# PIC-adresseur.net
KiCad netlist of a schematic drawn in EAGLE
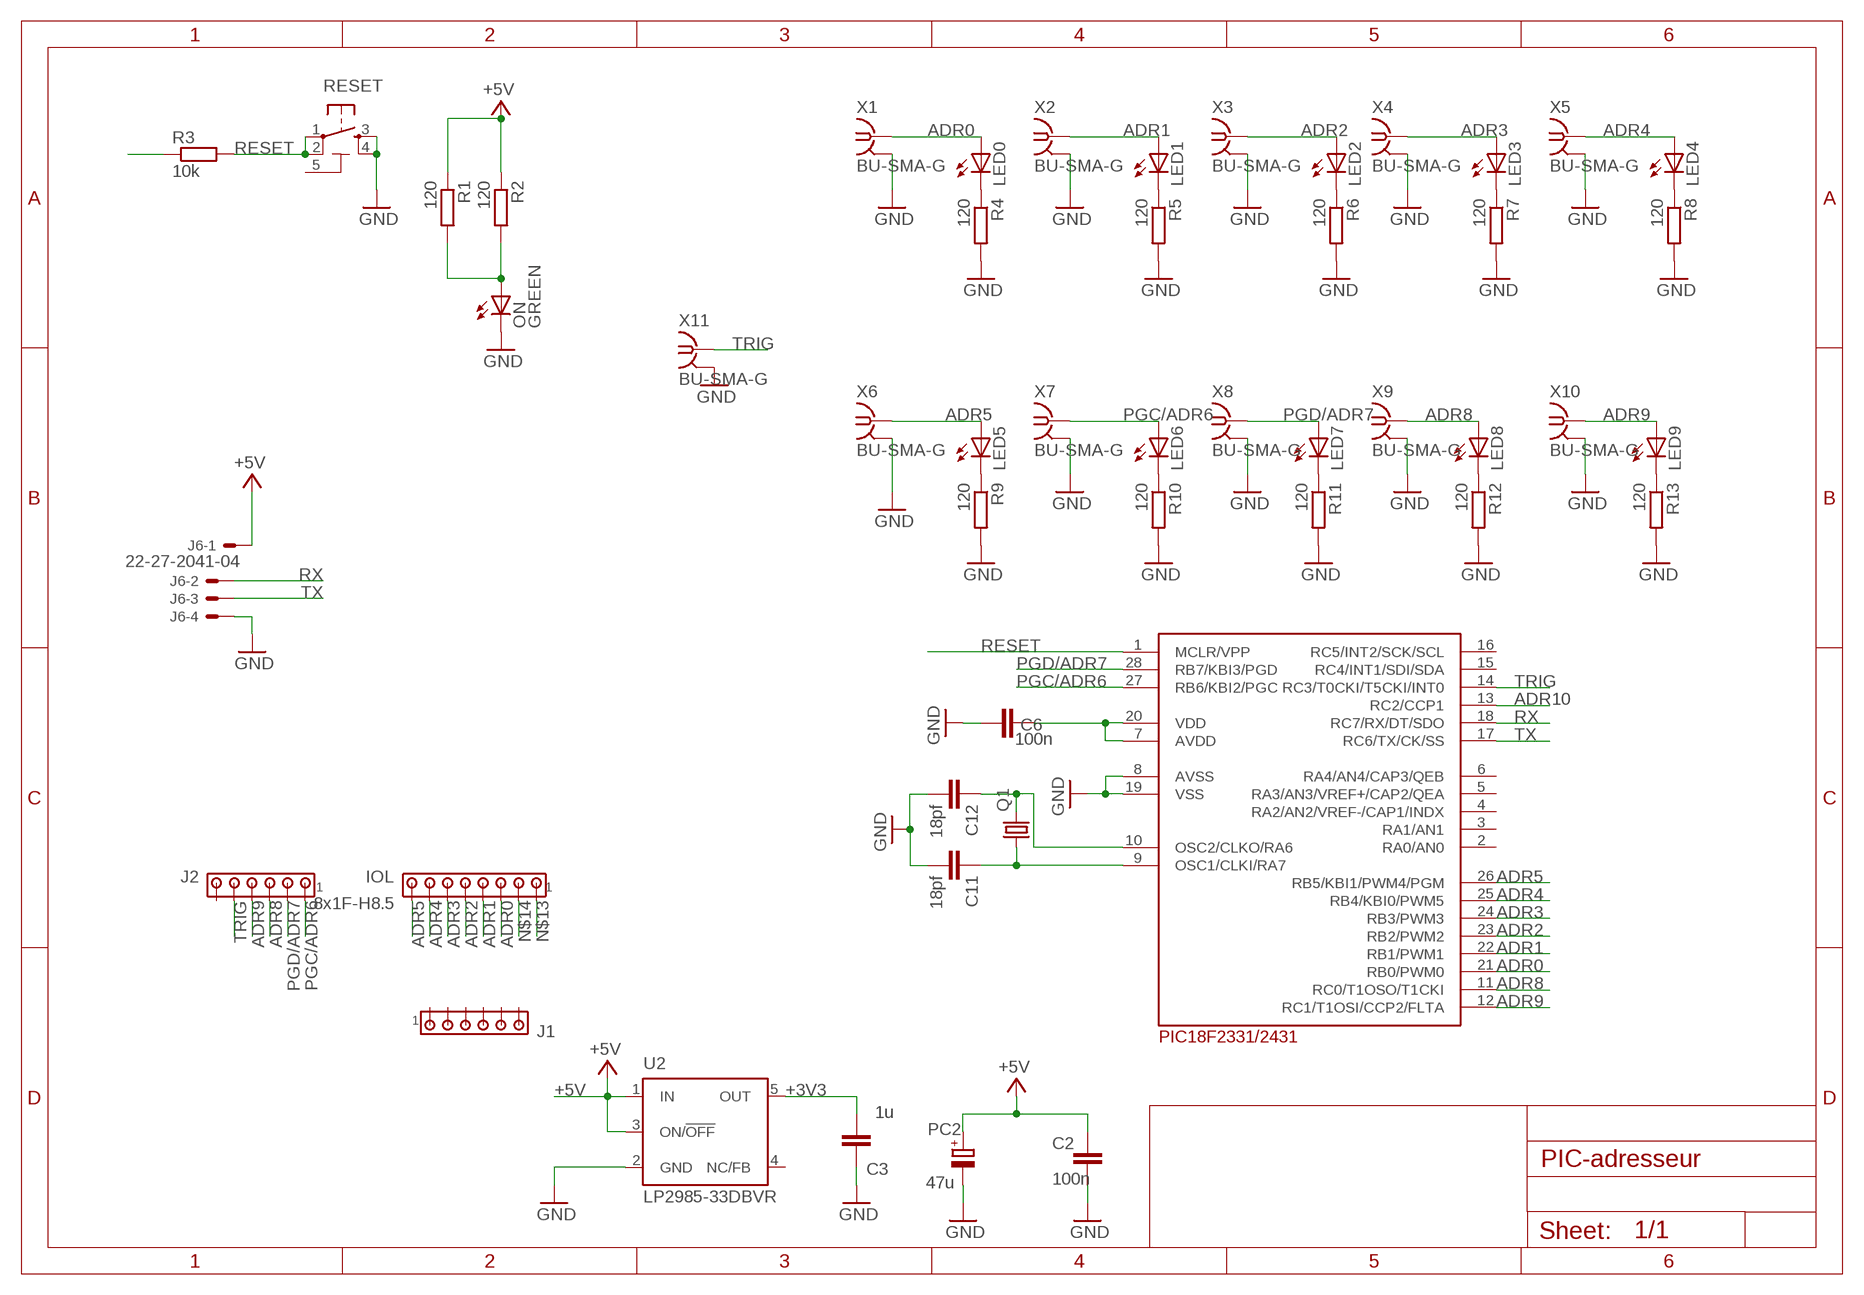
[diagram p0: schematic, sheet 1]

(export (version "E")
  (design (tool "Eeschema 10.0.6"))
  (components
    (comp (ref "C2")
      (value "100n")
      (footprint "eagle-import:C0603-ROUND")
      (libsource (lib "eagle-import") (part "C-EU0603-RND"))
    )
    (comp (ref "C3")
      (value "1u")
      (footprint "eagle-import:C0603-ROUND")
      (libsource (lib "eagle-import") (part "C-EU0603-RND"))
    )
    (comp (ref "C6")
      (value "100n")
      (footprint "eagle-import:C0603K")
      (libsource (lib "eagle-import") (part "SmartPrj_C-EUC0603K"))
    )
    (comp (ref "C11")
      (value "18pf")
      (footprint "eagle-import:C0603")
      (libsource (lib "eagle-import") (part "C-EUC0603"))
    )
    (comp (ref "C12")
      (value "18pf")
      (footprint "eagle-import:C0603")
      (libsource (lib "eagle-import") (part "C-EUC0603"))
    )
    (comp (ref "IOL")
      (value "8x1F-H8.5")
      (footprint "eagle-import:10X08MTA")
      (libsource (lib "eagle-import") (part "MTA08-100"))
    )
    (comp (ref "J1")
      (value "MTA06-100")
      (footprint "eagle-import:10X06MTA")
      (libsource (lib "eagle-import") (part "MTA06-100"))
    )
    (comp (ref "J2")
      (value "MTA06-100")
      (footprint "eagle-import:10X06MTA")
      (libsource (lib "eagle-import") (part "MTA06-100"))
    )
    (comp (ref "J6")
      (value "22-27-2041-04")
      (footprint "eagle-import:6410-04")
      (libsource (lib "eagle-import") (part "22-?-0427-2041"))
    )
    (comp (ref "LED0")
      (value "LEDCHIP-LED0805")
      (footprint "eagle-import:CHIP-LED0805")
      (libsource (lib "eagle-import") (part "LEDCHIP-LED0805"))
    )
    (comp (ref "LED1")
      (value "LEDCHIP-LED0805")
      (footprint "eagle-import:CHIP-LED0805")
      (libsource (lib "eagle-import") (part "LEDCHIP-LED0805"))
    )
    (comp (ref "LED2")
      (value "LEDCHIP-LED0805")
      (footprint "eagle-import:CHIP-LED0805")
      (libsource (lib "eagle-import") (part "LEDCHIP-LED0805"))
    )
    (comp (ref "LED3")
      (value "LEDCHIP-LED0805")
      (footprint "eagle-import:CHIP-LED0805")
      (libsource (lib "eagle-import") (part "LEDCHIP-LED0805"))
    )
    (comp (ref "LED4")
      (value "LEDCHIP-LED0805")
      (footprint "eagle-import:CHIP-LED0805")
      (libsource (lib "eagle-import") (part "LEDCHIP-LED0805"))
    )
    (comp (ref "LED5")
      (value "LEDCHIP-LED0805")
      (footprint "eagle-import:CHIP-LED0805")
      (libsource (lib "eagle-import") (part "LEDCHIP-LED0805"))
    )
    (comp (ref "LED6")
      (value "LEDCHIP-LED0805")
      (footprint "eagle-import:CHIP-LED0805")
      (libsource (lib "eagle-import") (part "LEDCHIP-LED0805"))
    )
    (comp (ref "LED7")
      (value "LEDCHIP-LED0805")
      (footprint "eagle-import:CHIP-LED0805")
      (libsource (lib "eagle-import") (part "LEDCHIP-LED0805"))
    )
    (comp (ref "LED8")
      (value "LEDCHIP-LED0805")
      (footprint "eagle-import:CHIP-LED0805")
      (libsource (lib "eagle-import") (part "LEDCHIP-LED0805"))
    )
    (comp (ref "LED9")
      (value "LEDCHIP-LED0805")
      (footprint "eagle-import:CHIP-LED0805")
      (libsource (lib "eagle-import") (part "LEDCHIP-LED0805"))
    )
    (comp (ref "ON")
      (value "GREEN")
      (footprint "eagle-import:CHIP-LED0805")
      (libsource (lib "eagle-import") (part "led_LEDCHIP-LED0805"))
    )
    (comp (ref "PC2")
      (value "47u")
      (footprint "eagle-import:PANASONIC_D")
      (libsource (lib "eagle-import") (part "CPOL-EUD"))
    )
    (comp (ref "Q1")
      (value "CRYSTALSM49")
      (footprint "eagle-import:SM49")
      (fields (field (name "OC_FARNELL") "1842332"))
      (libsource (lib "eagle-import") (part "CRYSTALSM49"))
    )
    (comp (ref "R1")
      (value "120")
      (footprint "eagle-import:R0805")
      (libsource (lib "eagle-import") (part "R-EU_R0805"))
    )
    (comp (ref "R2")
      (value "120")
      (footprint "eagle-import:R0805")
      (libsource (lib "eagle-import") (part "R-EU_R0805"))
    )
    (comp (ref "R3")
      (value "10k")
      (footprint "eagle-import:R0805")
      (libsource (lib "eagle-import") (part "R-EU_R0805"))
    )
    (comp (ref "R4")
      (value "120")
      (footprint "eagle-import:R0805")
      (libsource (lib "eagle-import") (part "R-EU_R0805"))
    )
    (comp (ref "R5")
      (value "120")
      (footprint "eagle-import:R0805")
      (libsource (lib "eagle-import") (part "R-EU_R0805"))
    )
    (comp (ref "R6")
      (value "120")
      (footprint "eagle-import:R0805")
      (libsource (lib "eagle-import") (part "R-EU_R0805"))
    )
    (comp (ref "R7")
      (value "120")
      (footprint "eagle-import:R0805")
      (libsource (lib "eagle-import") (part "R-EU_R0805"))
    )
    (comp (ref "R8")
      (value "120")
      (footprint "eagle-import:R0805")
      (libsource (lib "eagle-import") (part "R-EU_R0805"))
    )
    (comp (ref "R9")
      (value "120")
      (footprint "eagle-import:R0805")
      (libsource (lib "eagle-import") (part "R-EU_R0805"))
    )
    (comp (ref "R10")
      (value "120")
      (footprint "eagle-import:R0805")
      (libsource (lib "eagle-import") (part "R-EU_R0805"))
    )
    (comp (ref "R11")
      (value "120")
      (footprint "eagle-import:R0805")
      (libsource (lib "eagle-import") (part "R-EU_R0805"))
    )
    (comp (ref "R12")
      (value "120")
      (footprint "eagle-import:R0805")
      (libsource (lib "eagle-import") (part "R-EU_R0805"))
    )
    (comp (ref "R13")
      (value "120")
      (footprint "eagle-import:R0805")
      (libsource (lib "eagle-import") (part "R-EU_R0805"))
    )
    (comp (ref "RESET")
      (value "TS42031-160R-TR-7260")
      (footprint "eagle-import:TS42")
      (libsource (lib "eagle-import") (part "TS42"))
    )
    (comp (ref "U$2")
      (value "PIC18F2331/2431")
      (footprint "eagle-import:DIL28-3")
      (libsource (lib "eagle-import") (part "PIC18F2331/2431"))
    )
    (comp (ref "U2")
      (value "LP2985-33DBVR")
      (footprint "eagle-import:SOT23-DBV")
      (libsource (lib "eagle-import") (part "LP2985-XXDBVR33"))
    )
    (comp (ref "X1")
      (value "BU-SMA-G")
      (footprint "eagle-import:BU-SMA-G")
      (libsource (lib "eagle-import") (part "BU-SMA-G"))
    )
    (comp (ref "X2")
      (value "BU-SMA-G")
      (footprint "eagle-import:BU-SMA-G")
      (libsource (lib "eagle-import") (part "BU-SMA-G"))
    )
    (comp (ref "X3")
      (value "BU-SMA-G")
      (footprint "eagle-import:BU-SMA-G")
      (libsource (lib "eagle-import") (part "BU-SMA-G"))
    )
    (comp (ref "X4")
      (value "BU-SMA-G")
      (footprint "eagle-import:BU-SMA-G")
      (libsource (lib "eagle-import") (part "BU-SMA-G"))
    )
    (comp (ref "X5")
      (value "BU-SMA-G")
      (footprint "eagle-import:BU-SMA-G")
      (libsource (lib "eagle-import") (part "BU-SMA-G"))
    )
    (comp (ref "X6")
      (value "BU-SMA-G")
      (footprint "eagle-import:BU-SMA-G")
      (libsource (lib "eagle-import") (part "BU-SMA-G"))
    )
    (comp (ref "X7")
      (value "BU-SMA-G")
      (footprint "eagle-import:BU-SMA-G")
      (libsource (lib "eagle-import") (part "BU-SMA-G"))
    )
    (comp (ref "X8")
      (value "BU-SMA-G")
      (footprint "eagle-import:BU-SMA-G")
      (libsource (lib "eagle-import") (part "BU-SMA-G"))
    )
    (comp (ref "X9")
      (value "BU-SMA-G")
      (footprint "eagle-import:BU-SMA-G")
      (libsource (lib "eagle-import") (part "BU-SMA-G"))
    )
    (comp (ref "X10")
      (value "BU-SMA-G")
      (footprint "eagle-import:BU-SMA-G")
      (libsource (lib "eagle-import") (part "BU-SMA-G"))
    )
    (comp (ref "X11")
      (value "BU-SMA-G")
      (footprint "eagle-import:BU-SMA-G")
      (libsource (lib "eagle-import") (part "BU-SMA-G"))
    )
  )
  (nets
    (net (code "1") (name "+5V") (class "Default")
      (node (ref "C2") (pin "2") (pinfunction "2_2") (pintype "passive"))
      (node (ref "J6") (pin "1") (pinfunction "S_1") (pintype "passive"))
      (node (ref "PC2") (pin "+") (pinfunction "+_+") (pintype "passive"))
      (node (ref "R1") (pin "1") (pinfunction "1_1") (pintype "passive"))
      (node (ref "R2") (pin "1") (pinfunction "1_1") (pintype "passive"))
      (node (ref "U2") (pin "1") (pinfunction "IN_1") (pintype "input"))
      (node (ref "U2") (pin "3") (pinfunction "ON/~{OFF}_3") (pintype "input"))
    )
    (net (code "2") (name "/+3V3") (class "Default")
      (node (ref "C3") (pin "2") (pinfunction "2_2") (pintype "passive"))
      (node (ref "C6") (pin "2") (pinfunction "2_2") (pintype "passive"))
      (node (ref "R3") (pin "1") (pinfunction "1_1") (pintype "passive"))
      (node (ref "U$2") (pin "20") (pinfunction "VDD_20") (pintype "bidirectional"))
      (node (ref "U$2") (pin "7") (pinfunction "AVDD_7") (pintype "bidirectional"))
      (node (ref "U2") (pin "5") (pinfunction "OUT_5") (pintype "passive"))
    )
    (net (code "3") (name "/5-GND") (class "Default")
      (node (ref "RESET") (pin "5") (pinfunction "5-GND_5") (pintype "power_in"))
    )
    (net (code "4") (name "/ADR0") (class "Default")
      (node (ref "IOL") (pin "3") (pinfunction "3_3") (pintype "passive"))
      (node (ref "LED0") (pin "A") (pinfunction "A_A") (pintype "passive"))
      (node (ref "U$2") (pin "21") (pinfunction "RB0/PWM0_21") (pintype "bidirectional"))
      (node (ref "X1") (pin "1") (pinfunction "1_1") (pintype "passive"))
    )
    (net (code "5") (name "/ADR1") (class "Default")
      (node (ref "IOL") (pin "4") (pinfunction "4_4") (pintype "passive"))
      (node (ref "LED1") (pin "A") (pinfunction "A_A") (pintype "passive"))
      (node (ref "U$2") (pin "22") (pinfunction "RB1/PWM1_22") (pintype "bidirectional"))
      (node (ref "X2") (pin "1") (pinfunction "1_1") (pintype "passive"))
    )
    (net (code "6") (name "/ADR2") (class "Default")
      (node (ref "IOL") (pin "5") (pinfunction "5_5") (pintype "passive"))
      (node (ref "LED2") (pin "A") (pinfunction "A_A") (pintype "passive"))
      (node (ref "U$2") (pin "23") (pinfunction "RB2/PWM2_23") (pintype "bidirectional"))
      (node (ref "X3") (pin "1") (pinfunction "1_1") (pintype "passive"))
    )
    (net (code "7") (name "/ADR3") (class "Default")
      (node (ref "IOL") (pin "6") (pinfunction "6_6") (pintype "passive"))
      (node (ref "LED3") (pin "A") (pinfunction "A_A") (pintype "passive"))
      (node (ref "U$2") (pin "24") (pinfunction "RB3/PWM3_24") (pintype "bidirectional"))
      (node (ref "X4") (pin "1") (pinfunction "1_1") (pintype "passive"))
    )
    (net (code "8") (name "/ADR4") (class "Default")
      (node (ref "IOL") (pin "7") (pinfunction "7_7") (pintype "passive"))
      (node (ref "LED4") (pin "A") (pinfunction "A_A") (pintype "passive"))
      (node (ref "U$2") (pin "25") (pinfunction "RB4/KBI0/PWM5_25") (pintype "bidirectional"))
      (node (ref "X5") (pin "1") (pinfunction "1_1") (pintype "passive"))
    )
    (net (code "9") (name "/ADR5") (class "Default")
      (node (ref "IOL") (pin "8") (pinfunction "8_8") (pintype "passive"))
      (node (ref "LED5") (pin "A") (pinfunction "A_A") (pintype "passive"))
      (node (ref "U$2") (pin "26") (pinfunction "RB5/KBI1/PWM4/PGM_26") (pintype "bidirectional"))
      (node (ref "X6") (pin "1") (pinfunction "1_1") (pintype "passive"))
    )
    (net (code "10") (name "/ADR8") (class "Default")
      (node (ref "J2") (pin "4") (pinfunction "3_4") (pintype "passive"))
      (node (ref "LED8") (pin "A") (pinfunction "A_A") (pintype "passive"))
      (node (ref "U$2") (pin "11") (pinfunction "RC0/T1OSO/T1CKI_11") (pintype "bidirectional"))
      (node (ref "X9") (pin "1") (pinfunction "1_1") (pintype "passive"))
    )
    (net (code "11") (name "/ADR9") (class "Default")
      (node (ref "J2") (pin "3") (pinfunction "4_3") (pintype "passive"))
      (node (ref "LED9") (pin "A") (pinfunction "A_A") (pintype "passive"))
      (node (ref "U$2") (pin "12") (pinfunction "RC1/T1OSI/CCP2/FLTA_12") (pintype "bidirectional"))
      (node (ref "X10") (pin "1") (pinfunction "1_1") (pintype "passive"))
    )
    (net (code "12") (name "/ADR10") (class "Default")
      (node (ref "U$2") (pin "13") (pinfunction "RC2/CCP1_13") (pintype "bidirectional"))
    )
    (net (code "13") (name "/N$13") (class "Default")
      (node (ref "IOL") (pin "1") (pinfunction "1_1") (pintype "passive"))
    )
    (net (code "14") (name "/N$14") (class "Default")
      (node (ref "IOL") (pin "2") (pinfunction "2_2") (pintype "passive"))
    )
    (net (code "15") (name "/PGC{slash}ADR6") (class "Default")
      (node (ref "J2") (pin "6") (pinfunction "1_6") (pintype "passive"))
      (node (ref "LED6") (pin "A") (pinfunction "A_A") (pintype "passive"))
      (node (ref "U$2") (pin "27") (pinfunction "RB6/KBI2/PGC_27") (pintype "bidirectional"))
      (node (ref "X7") (pin "1") (pinfunction "1_1") (pintype "passive"))
    )
    (net (code "16") (name "/PGD{slash}ADR7") (class "Default")
      (node (ref "J2") (pin "5") (pinfunction "2_5") (pintype "passive"))
      (node (ref "LED7") (pin "A") (pinfunction "A_A") (pintype "passive"))
      (node (ref "U$2") (pin "28") (pinfunction "RB7/KBI3/PGD_28") (pintype "bidirectional"))
      (node (ref "X8") (pin "1") (pinfunction "1_1") (pintype "passive"))
    )
    (net (code "17") (name "/RESET") (class "Default")
      (node (ref "R3") (pin "2") (pinfunction "2_2") (pintype "passive"))
      (node (ref "RESET") (pin "1") (pinfunction "1_1") (pintype "passive"))
      (node (ref "RESET") (pin "2") (pinfunction "2_2") (pintype "passive"))
      (node (ref "U$2") (pin "1") (pinfunction "MCLR/VPP_1") (pintype "bidirectional"))
    )
    (net (code "18") (name "/RX") (class "Default")
      (node (ref "J6") (pin "2") (pinfunction "S_2") (pintype "passive"))
      (node (ref "U$2") (pin "18") (pinfunction "RC7/RX/DT/SDO_18") (pintype "bidirectional"))
    )
    (net (code "19") (name "/TRIG") (class "Default")
      (node (ref "J2") (pin "2") (pinfunction "5_2") (pintype "passive"))
      (node (ref "U$2") (pin "14") (pinfunction "RC3/T0CKI/T5CKI/INT0_14") (pintype "bidirectional"))
      (node (ref "X11") (pin "1") (pinfunction "1_1") (pintype "passive"))
    )
    (net (code "20") (name "/TX") (class "Default")
      (node (ref "J6") (pin "3") (pinfunction "S_3") (pintype "passive"))
      (node (ref "U$2") (pin "17") (pinfunction "RC6/TX/CK/SS_17") (pintype "bidirectional"))
    )
    (net (code "21") (name "GND") (class "Default")
      (node (ref "C11") (pin "2") (pinfunction "2_2") (pintype "passive"))
      (node (ref "C12") (pin "2") (pinfunction "2_2") (pintype "passive"))
      (node (ref "C2") (pin "1") (pinfunction "1_1") (pintype "passive"))
      (node (ref "C3") (pin "1") (pinfunction "1_1") (pintype "passive"))
      (node (ref "C6") (pin "1") (pinfunction "1_1") (pintype "passive"))
      (node (ref "J6") (pin "4") (pinfunction "S_4") (pintype "passive"))
      (node (ref "ON") (pin "C") (pinfunction "C_C") (pintype "passive"))
      (node (ref "PC2") (pin "-") (pinfunction "-_-") (pintype "passive"))
      (node (ref "R10") (pin "2") (pinfunction "2_2") (pintype "passive"))
      (node (ref "R11") (pin "2") (pinfunction "2_2") (pintype "passive"))
      (node (ref "R12") (pin "2") (pinfunction "2_2") (pintype "passive"))
      (node (ref "R13") (pin "2") (pinfunction "2_2") (pintype "passive"))
      (node (ref "R4") (pin "2") (pinfunction "2_2") (pintype "passive"))
      (node (ref "R5") (pin "2") (pinfunction "2_2") (pintype "passive"))
      (node (ref "R6") (pin "2") (pinfunction "2_2") (pintype "passive"))
      (node (ref "R7") (pin "2") (pinfunction "2_2") (pintype "passive"))
      (node (ref "R8") (pin "2") (pinfunction "2_2") (pintype "passive"))
      (node (ref "R9") (pin "2") (pinfunction "2_2") (pintype "passive"))
      (node (ref "RESET") (pin "3") (pinfunction "3_3") (pintype "passive"))
      (node (ref "RESET") (pin "4") (pinfunction "4_4") (pintype "passive"))
      (node (ref "U$2") (pin "19") (pinfunction "VSS_19") (pintype "bidirectional"))
      (node (ref "U$2") (pin "8") (pinfunction "AVSS_8") (pintype "bidirectional"))
      (node (ref "U2") (pin "2") (pinfunction "GND_2") (pintype "power_in"))
      (node (ref "X1") (pin "2") (pinfunction "2_2") (pintype "passive"))
      (node (ref "X1") (pin "3") (pinfunction "2_3") (pintype "passive"))
      (node (ref "X1") (pin "4") (pinfunction "2_4") (pintype "passive"))
      (node (ref "X1") (pin "5") (pinfunction "2_5") (pintype "passive"))
      (node (ref "X10") (pin "2") (pinfunction "2_2") (pintype "passive"))
      (node (ref "X10") (pin "3") (pinfunction "2_3") (pintype "passive"))
      (node (ref "X10") (pin "4") (pinfunction "2_4") (pintype "passive"))
      (node (ref "X10") (pin "5") (pinfunction "2_5") (pintype "passive"))
      (node (ref "X11") (pin "2") (pinfunction "2_2") (pintype "passive"))
      (node (ref "X11") (pin "3") (pinfunction "2_3") (pintype "passive"))
      (node (ref "X11") (pin "4") (pinfunction "2_4") (pintype "passive"))
      (node (ref "X11") (pin "5") (pinfunction "2_5") (pintype "passive"))
      (node (ref "X2") (pin "2") (pinfunction "2_2") (pintype "passive"))
      (node (ref "X2") (pin "3") (pinfunction "2_3") (pintype "passive"))
      (node (ref "X2") (pin "4") (pinfunction "2_4") (pintype "passive"))
      (node (ref "X2") (pin "5") (pinfunction "2_5") (pintype "passive"))
      (node (ref "X3") (pin "2") (pinfunction "2_2") (pintype "passive"))
      (node (ref "X3") (pin "3") (pinfunction "2_3") (pintype "passive"))
      (node (ref "X3") (pin "4") (pinfunction "2_4") (pintype "passive"))
      (node (ref "X3") (pin "5") (pinfunction "2_5") (pintype "passive"))
      (node (ref "X4") (pin "2") (pinfunction "2_2") (pintype "passive"))
      (node (ref "X4") (pin "3") (pinfunction "2_3") (pintype "passive"))
      (node (ref "X4") (pin "4") (pinfunction "2_4") (pintype "passive"))
      (node (ref "X4") (pin "5") (pinfunction "2_5") (pintype "passive"))
      (node (ref "X5") (pin "2") (pinfunction "2_2") (pintype "passive"))
      (node (ref "X5") (pin "3") (pinfunction "2_3") (pintype "passive"))
      (node (ref "X5") (pin "4") (pinfunction "2_4") (pintype "passive"))
      (node (ref "X5") (pin "5") (pinfunction "2_5") (pintype "passive"))
      (node (ref "X6") (pin "2") (pinfunction "2_2") (pintype "passive"))
      (node (ref "X6") (pin "3") (pinfunction "2_3") (pintype "passive"))
      (node (ref "X6") (pin "4") (pinfunction "2_4") (pintype "passive"))
      (node (ref "X6") (pin "5") (pinfunction "2_5") (pintype "passive"))
      (node (ref "X7") (pin "2") (pinfunction "2_2") (pintype "passive"))
      (node (ref "X7") (pin "3") (pinfunction "2_3") (pintype "passive"))
      (node (ref "X7") (pin "4") (pinfunction "2_4") (pintype "passive"))
      (node (ref "X7") (pin "5") (pinfunction "2_5") (pintype "passive"))
      (node (ref "X8") (pin "2") (pinfunction "2_2") (pintype "passive"))
      (node (ref "X8") (pin "3") (pinfunction "2_3") (pintype "passive"))
      (node (ref "X8") (pin "4") (pinfunction "2_4") (pintype "passive"))
      (node (ref "X8") (pin "5") (pinfunction "2_5") (pintype "passive"))
      (node (ref "X9") (pin "2") (pinfunction "2_2") (pintype "passive"))
      (node (ref "X9") (pin "3") (pinfunction "2_3") (pintype "passive"))
      (node (ref "X9") (pin "4") (pinfunction "2_4") (pintype "passive"))
      (node (ref "X9") (pin "5") (pinfunction "2_5") (pintype "passive"))
    )
    (net (code "22") (name "Net-(LED0-PadC)") (class "Default")
      (node (ref "LED0") (pin "C") (pinfunction "C_C") (pintype "passive"))
      (node (ref "R4") (pin "1") (pinfunction "1_1") (pintype "passive"))
    )
    (net (code "23") (name "Net-(LED1-PadC)") (class "Default")
      (node (ref "LED1") (pin "C") (pinfunction "C_C") (pintype "passive"))
      (node (ref "R5") (pin "1") (pinfunction "1_1") (pintype "passive"))
    )
    (net (code "24") (name "Net-(LED2-PadC)") (class "Default")
      (node (ref "LED2") (pin "C") (pinfunction "C_C") (pintype "passive"))
      (node (ref "R6") (pin "1") (pinfunction "1_1") (pintype "passive"))
    )
    (net (code "25") (name "Net-(LED3-PadC)") (class "Default")
      (node (ref "LED3") (pin "C") (pinfunction "C_C") (pintype "passive"))
      (node (ref "R7") (pin "1") (pinfunction "1_1") (pintype "passive"))
    )
    (net (code "26") (name "Net-(LED4-PadC)") (class "Default")
      (node (ref "LED4") (pin "C") (pinfunction "C_C") (pintype "passive"))
      (node (ref "R8") (pin "1") (pinfunction "1_1") (pintype "passive"))
    )
    (net (code "27") (name "Net-(LED5-PadC)") (class "Default")
      (node (ref "LED5") (pin "C") (pinfunction "C_C") (pintype "passive"))
      (node (ref "R9") (pin "1") (pinfunction "1_1") (pintype "passive"))
    )
    (net (code "28") (name "Net-(LED6-PadC)") (class "Default")
      (node (ref "LED6") (pin "C") (pinfunction "C_C") (pintype "passive"))
      (node (ref "R10") (pin "1") (pinfunction "1_1") (pintype "passive"))
    )
    (net (code "29") (name "Net-(LED7-PadC)") (class "Default")
      (node (ref "LED7") (pin "C") (pinfunction "C_C") (pintype "passive"))
      (node (ref "R11") (pin "1") (pinfunction "1_1") (pintype "passive"))
    )
    (net (code "30") (name "Net-(LED8-PadC)") (class "Default")
      (node (ref "LED8") (pin "C") (pinfunction "C_C") (pintype "passive"))
      (node (ref "R12") (pin "1") (pinfunction "1_1") (pintype "passive"))
    )
    (net (code "31") (name "Net-(LED9-PadC)") (class "Default")
      (node (ref "LED9") (pin "C") (pinfunction "C_C") (pintype "passive"))
      (node (ref "R13") (pin "1") (pinfunction "1_1") (pintype "passive"))
    )
    (net (code "32") (name "Net-(ON-PadA)") (class "Default")
      (node (ref "ON") (pin "A") (pinfunction "A_A") (pintype "passive"))
      (node (ref "R1") (pin "2") (pinfunction "2_2") (pintype "passive"))
      (node (ref "R2") (pin "2") (pinfunction "2_2") (pintype "passive"))
    )
    (net (code "33") (name "Net-(U$2-OSC1{slash}CLKI{slash}RA7)") (class "Default")
      (node (ref "C11") (pin "1") (pinfunction "1_1") (pintype "passive"))
      (node (ref "Q1") (pin "1") (pinfunction "1_1") (pintype "passive"))
      (node (ref "U$2") (pin "9") (pinfunction "OSC1/CLKI/RA7_9") (pintype "bidirectional"))
    )
    (net (code "34") (name "Net-(U$2-OSC2{slash}CLKO{slash}RA6)") (class "Default")
      (node (ref "C12") (pin "1") (pinfunction "1_1") (pintype "passive"))
      (node (ref "Q1") (pin "2") (pinfunction "2_2") (pintype "passive"))
      (node (ref "U$2") (pin "10") (pinfunction "OSC2/CLKO/RA6_10") (pintype "bidirectional"))
    )
    (net (code "35") (name "unconnected-(J1-1-Pad6)") (class "Default")
      (node (ref "J1") (pin "6") (pinfunction "1_6") (pintype "passive"))
    )
    (net (code "36") (name "unconnected-(J1-2-Pad5)") (class "Default")
      (node (ref "J1") (pin "5") (pinfunction "2_5") (pintype "passive"))
    )
    (net (code "37") (name "unconnected-(J1-3-Pad4)") (class "Default")
      (node (ref "J1") (pin "4") (pinfunction "3_4") (pintype "passive"))
    )
    (net (code "38") (name "unconnected-(J1-4-Pad3)") (class "Default")
      (node (ref "J1") (pin "3") (pinfunction "4_3") (pintype "passive"))
    )
    (net (code "39") (name "unconnected-(J1-5-Pad2)") (class "Default")
      (node (ref "J1") (pin "2") (pinfunction "5_2") (pintype "passive"))
    )
    (net (code "40") (name "unconnected-(J1-6-Pad1)") (class "Default")
      (node (ref "J1") (pin "1") (pinfunction "6_1") (pintype "passive"))
    )
    (net (code "41") (name "unconnected-(J2-6-Pad1)") (class "Default")
      (node (ref "J2") (pin "1") (pinfunction "6_1") (pintype "passive"))
    )
    (net (code "42") (name "unconnected-(U$2-RA0{slash}AN0-Pad2)") (class "Default")
      (node (ref "U$2") (pin "2") (pinfunction "RA0/AN0_2") (pintype "bidirectional"))
    )
    (net (code "43") (name "unconnected-(U$2-RA1{slash}AN1-Pad3)") (class "Default")
      (node (ref "U$2") (pin "3") (pinfunction "RA1/AN1_3") (pintype "bidirectional"))
    )
    (net (code "44") (name "unconnected-(U$2-RA2{slash}AN2{slash}VREF-{slash}CAP1{slash}INDX-Pad4)") (class "Default")
      (node (ref "U$2") (pin "4") (pinfunction "RA2/AN2/VREF-/CAP1/INDX_4") (pintype "bidirectional"))
    )
    (net (code "45") (name "unconnected-(U$2-RA3{slash}AN3{slash}VREF+{slash}CAP2{slash}QEA-Pad5)") (class "Default")
      (node (ref "U$2") (pin "5") (pinfunction "RA3/AN3/VREF+/CAP2/QEA_5") (pintype "bidirectional"))
    )
    (net (code "46") (name "unconnected-(U$2-RA4{slash}AN4{slash}CAP3{slash}QEB-Pad6)") (class "Default")
      (node (ref "U$2") (pin "6") (pinfunction "RA4/AN4/CAP3/QEB_6") (pintype "bidirectional"))
    )
    (net (code "47") (name "unconnected-(U$2-RC4{slash}INT1{slash}SDI{slash}SDA-Pad15)") (class "Default")
      (node (ref "U$2") (pin "15") (pinfunction "RC4/INT1/SDI/SDA_15") (pintype "bidirectional"))
    )
    (net (code "48") (name "unconnected-(U$2-RC5{slash}INT2{slash}SCK{slash}SCL-Pad16)") (class "Default")
      (node (ref "U$2") (pin "16") (pinfunction "RC5/INT2/SCK/SCL_16") (pintype "bidirectional"))
    )
    (net (code "49") (name "unconnected-(U2-NC{slash}FB-Pad4)") (class "Default")
      (node (ref "U2") (pin "4") (pinfunction "NC/FB_4") (pintype "passive"))
    )
  )
)
